# PDOC.net
KiCad netlist of a schematic drawn in Altium Designer
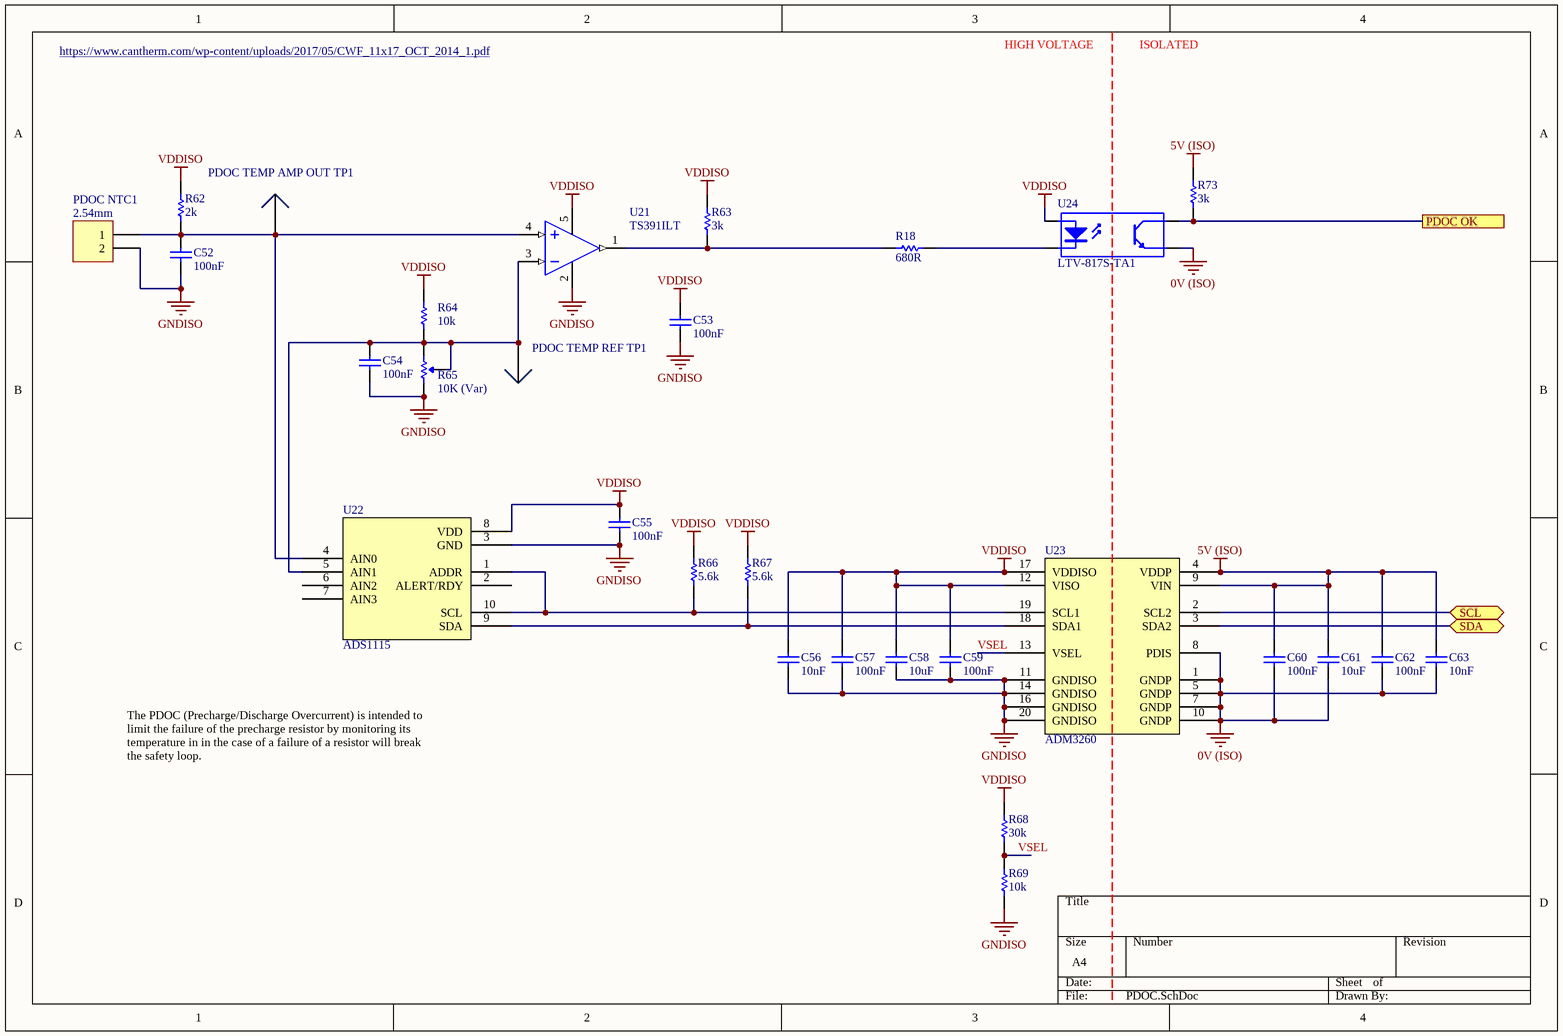
[diagram p0: PDOC.SchDoc]

(export (version "E")
  (design (tool "Eeschema 10.0.6"))
  (components
    (comp (ref "C52")
      (value "100nF")
      (footprint "0805")
      (fields
        (field (name "PART NUMBER") "GCM21BR71E104KA37L")
        (field (name "TOLERANCE") "10%")
        (field (name "MANUFACTURER") "muRata")
      )
      (libsource (lib "ts_20-standard-library") (part "Capacitor"))
    )
    (comp (ref "C53")
      (value "100nF")
      (footprint "0805")
      (fields
        (field (name "PART NUMBER") "GCM21BR71E104KA37L")
        (field (name "TOLERANCE") "10%")
        (field (name "MANUFACTURER") "muRata")
      )
      (libsource (lib "ts_20-standard-library") (part "Capacitor"))
    )
    (comp (ref "C54")
      (value "100nF")
      (footprint "0805")
      (fields
        (field (name "PART NUMBER") "GCM21BR71E104KA37L")
        (field (name "TOLERANCE") "10%")
        (field (name "MANUFACTURER") "muRata")
      )
      (libsource (lib "ts_20-standard-library") (part "Capacitor"))
    )
    (comp (ref "C55")
      (value "100nF")
      (footprint "0805")
      (fields
        (field (name "PART NUMBER") "GCM21BR71E104KA37L")
        (field (name "TOLERANCE") "10%")
        (field (name "MANUFACTURER") "muRata")
      )
      (libsource (lib "ts_20-standard-library") (part "Capacitor"))
    )
    (comp (ref "C56")
      (value "10nF")
      (footprint "0805")
      (fields
        (field (name "PART NUMBER") "GCM21BR71H103KA37L")
        (field (name "TOLERANCE") "10%")
        (field (name "MANUFACTURER") "muRata")
      )
      (libsource (lib "ts_20-standard-library") (part "Capacitor"))
    )
    (comp (ref "C57")
      (value "100nF")
      (footprint "0805")
      (fields
        (field (name "PART NUMBER") "GCM21BR71E104KA37L")
        (field (name "TOLERANCE") "10%")
        (field (name "MANUFACTURER") "muRata")
      )
      (libsource (lib "ts_20-standard-library") (part "Capacitor"))
    )
    (comp (ref "C58")
      (value "10uF")
      (footprint "0805")
      (fields
        (field (name "PART NUMBER") "GRM21BR6YA106KE43L")
        (field (name "TOLERANCE") "10%")
        (field (name "MANUFACTURER") "muRata")
      )
      (libsource (lib "ts_20-standard-library") (part "Capacitor"))
    )
    (comp (ref "C59")
      (value "100nF")
      (footprint "0805")
      (fields
        (field (name "PART NUMBER") "GCM21BR71E104KA37L")
        (field (name "TOLERANCE") "10%")
        (field (name "MANUFACTURER") "muRata")
      )
      (libsource (lib "ts_20-standard-library") (part "Capacitor"))
    )
    (comp (ref "C60")
      (value "100nF")
      (footprint "0805")
      (fields
        (field (name "PART NUMBER") "GCM21BR71E104KA37L")
        (field (name "TOLERANCE") "10%")
        (field (name "MANUFACTURER") "muRata")
      )
      (libsource (lib "ts_20-standard-library") (part "Capacitor"))
    )
    (comp (ref "C61")
      (value "10uF")
      (footprint "0805")
      (fields
        (field (name "PART NUMBER") "GRM21BR6YA106KE43L")
        (field (name "TOLERANCE") "10%")
        (field (name "MANUFACTURER") "muRata")
      )
      (libsource (lib "ts_20-standard-library") (part "Capacitor"))
    )
    (comp (ref "C62")
      (value "100nF")
      (footprint "0805")
      (fields
        (field (name "PART NUMBER") "GCM21BR71E104KA37L")
        (field (name "TOLERANCE") "10%")
        (field (name "MANUFACTURER") "muRata")
      )
      (libsource (lib "ts_20-standard-library") (part "Capacitor"))
    )
    (comp (ref "C63")
      (value "10nF")
      (footprint "0805")
      (fields
        (field (name "PART NUMBER") "GCM21BR71H103KA37L")
        (field (name "TOLERANCE") "10%")
        (field (name "MANUFACTURER") "muRata")
      )
      (libsource (lib "ts_20-standard-library") (part "Capacitor"))
    )
    (comp (ref "PDOC NTC1")
      (value "2.54mm")
      (footprint "TH 2.54mm Header 1x2")
      (fields (field (name "PART NUMBER") "TH 2.54mm Header 1x2") (field (name "CONTACT") "NA"))
      (libsource (lib "ts_20-standard-connectors") (part "Header 1x2"))
    )
    (comp (ref "PDOC TEMP AMP OUT TP1")
      (value "0mm")
      (footprint "SMD Test Point")
      (fields (field (name "PART NUMBER") "SMD Test Point") (field (name "CONTACT") "NA"))
      (libsource (lib "ts_20-standard-connectors") (part "Test Point"))
    )
    (comp (ref "PDOC TEMP REF TP1")
      (value "0mm")
      (footprint "SMD Test Point")
      (fields (field (name "PART NUMBER") "SMD Test Point") (field (name "CONTACT") "NA"))
      (libsource (lib "ts_20-standard-connectors") (part "Test Point"))
    )
    (comp (ref "R18")
      (value "680R")
      (footprint "0805")
      (fields
        (field (name "PART NUMBER") "RC0805FR07680RL")
        (field (name "MANUFACTURER") "YAGEO")
        (field (name "TOLERANCE") "0.01")
      )
      (libsource (lib "ts_20-standard-library") (part "Resistor"))
    )
    (comp (ref "R62")
      (value "2k")
      (footprint "0805")
      (fields
        (field (name "PART NUMBER") "RC0805FR072KL")
        (field (name "MANUFACTURER") "YAGEO")
        (field (name "TOLERANCE") "0.01")
      )
      (libsource (lib "ts_20-standard-library") (part "Resistor"))
    )
    (comp (ref "R63")
      (value "3k")
      (footprint "0805")
      (fields
        (field (name "PART NUMBER") "RC0805FR073KL")
        (field (name "MANUFACTURER") "YAGEO")
        (field (name "TOLERANCE") "0.01")
      )
      (libsource (lib "ts_20-standard-library") (part "Resistor"))
    )
    (comp (ref "R64")
      (value "10k")
      (footprint "0805")
      (fields
        (field (name "PART NUMBER") "RC0805FR0710KL")
        (field (name "MANUFACTURER") "YAGEO")
        (field (name "TOLERANCE") "0.01")
      )
      (libsource (lib "ts_20-standard-library") (part "Resistor"))
    )
    (comp (ref "R65")
      (value "10K (Var)")
      (footprint "B 3296")
      (fields
        (field (name "PART NUMBER") "3296W-1-103LF")
        (field (name "MANUFACTURER") "Bournes Inc")
        (field (name "TOLERANCE") "0.1")
      )
      (libsource (lib "ts_20-standard-library") (part "Resistor (Potentiometer)"))
    )
    (comp (ref "R66")
      (value "5.6k")
      (footprint "0805")
      (fields
        (field (name "PART NUMBER") "RC0805FR075K6L")
        (field (name "MANUFACTURER") "YAGEO")
        (field (name "TOLERANCE") "0.01")
      )
      (libsource (lib "ts_20-standard-library") (part "Resistor"))
    )
    (comp (ref "R67")
      (value "5.6k")
      (footprint "0805")
      (fields
        (field (name "PART NUMBER") "RC0805FR075K6L")
        (field (name "MANUFACTURER") "YAGEO")
        (field (name "TOLERANCE") "0.01")
      )
      (libsource (lib "ts_20-standard-library") (part "Resistor"))
    )
    (comp (ref "R68")
      (value "30k")
      (footprint "0805")
      (fields
        (field (name "PART NUMBER") "RC0805FR0730KL")
        (field (name "MANUFACTURER") "YAGEO")
        (field (name "TOLERANCE") "0.01")
      )
      (libsource (lib "ts_20-standard-library") (part "Resistor"))
    )
    (comp (ref "R69")
      (value "10k")
      (footprint "0805")
      (fields
        (field (name "PART NUMBER") "RC0805FR0710KL")
        (field (name "MANUFACTURER") "YAGEO")
        (field (name "TOLERANCE") "0.01")
      )
      (libsource (lib "ts_20-standard-library") (part "Resistor"))
    )
    (comp (ref "R73")
      (value "3k")
      (footprint "0805")
      (fields
        (field (name "PART NUMBER") "RC0805FR073KL")
        (field (name "MANUFACTURER") "YAGEO")
        (field (name "TOLERANCE") "0.01")
      )
      (libsource (lib "ts_20-standard-library") (part "Resistor"))
    )
    (comp (ref "U21")
      (value "TS391ILT")
      (footprint "ON SOT-23-5")
      (description "IC COMP LO PWR SGL V SOT 23-5L")
      (fields
        (field (name "MANUFACTURER") "STMicroelectronics")
        (field (name "DIGIKEY PART NUMBER") "497-2275-2-ND")
      )
      (libsource (lib "ts_20-standard-library") (part "TS391ILT"))
    )
    (comp (ref "U22")
      (value "ADS1115")
      (footprint "TI 10-VSSOP")
      (description "16 Bit Analog to Digital Converter 2, 4 Input 1 Sigma-Delta 10-VSSOP")
      (fields
        (field (name "MANUFACTURER") "Texas Instruments")
        (field (name "DIGIKEY PART NUMBER") "296-38849-1-ND")
      )
      (libsource (lib "ts_20-standard-library") (part "ADS1115"))
    )
    (comp (ref "U23")
      (value "ADM3260")
      (footprint "AD 20-SSOP")
      (description "I²C Digital Isolator 2500Vrms 2 Channel 25kV/µs CMTI 20-SSOP (0.209\", 5.30mm Width)")
      (fields
        (field (name "MANUFACTURER") "Analog Devices")
        (field (name "DIGIKEY PART NUMBER") "ADM3260ARSZ-RL7CT-ND")
      )
      (libsource (lib "ts_20-standard-library") (part "ADM3260"))
    )
    (comp (ref "U24")
      (value "LTV-817S-TA1")
      (footprint "ON 4-SMD")
      (description "35V 50ma Optocoupler (VF=1.2V)")
      (fields
        (field (name "MANUFACTURER") "Lite-On Inc")
        (field (name "DIGIKEY PART NUMBER") "160-1893-2-ND")
      )
      (libsource (lib "ts_20-standard-library") (part "LTV-817S-TA1"))
    )
  )
  (nets
    (net (code "1") (name "/PDOC OK") (class "Default")
      (node (ref "R73") (pin "1") (pinfunction "1_1") (pintype "passive"))
      (node (ref "U24") (pin "4") (pinfunction "C_4") (pintype "passive"))
    )
    (net (code "2") (name "/SCL") (class "Default")
      (node (ref "U23") (pin "2") (pinfunction "SCL2_2") (pintype "passive"))
    )
    (net (code "3") (name "/SDA") (class "Default")
      (node (ref "U23") (pin "3") (pinfunction "SDA2_3") (pintype "passive"))
    )
    (net (code "4") (name "/VSEL") (class "Default")
      (node (ref "R68") (pin "1") (pinfunction "1_1") (pintype "passive"))
      (node (ref "R69") (pin "2") (pinfunction "2_2") (pintype "passive"))
      (node (ref "U23") (pin "13") (pinfunction "VSEL_13") (pintype "passive"))
    )
    (net (code "5") (name "0V (ISO)") (class "Default")
      (node (ref "C60") (pin "1") (pinfunction "1_1") (pintype "passive"))
      (node (ref "C61") (pin "1") (pinfunction "1_1") (pintype "passive"))
      (node (ref "C62") (pin "1") (pinfunction "1_1") (pintype "passive"))
      (node (ref "C63") (pin "1") (pinfunction "1_1") (pintype "passive"))
      (node (ref "U23") (pin "1") (pinfunction "GNDP_1") (pintype "passive"))
      (node (ref "U23") (pin "10") (pinfunction "GNDP_10") (pintype "passive"))
      (node (ref "U23") (pin "5") (pinfunction "GNDP_5") (pintype "passive"))
      (node (ref "U23") (pin "7") (pinfunction "GNDP_7") (pintype "passive"))
      (node (ref "U23") (pin "8") (pinfunction "PDIS_8") (pintype "passive"))
      (node (ref "U24") (pin "3") (pinfunction "E_3") (pintype "passive"))
    )
    (net (code "6") (name "5V (ISO)") (class "Default")
      (node (ref "C60") (pin "2") (pinfunction "2_2") (pintype "passive"))
      (node (ref "C61") (pin "2") (pinfunction "2_2") (pintype "passive"))
      (node (ref "C62") (pin "2") (pinfunction "2_2") (pintype "passive"))
      (node (ref "C63") (pin "2") (pinfunction "2_2") (pintype "passive"))
      (node (ref "R73") (pin "2") (pinfunction "2_2") (pintype "passive"))
      (node (ref "U23") (pin "4") (pinfunction "VDDP_4") (pintype "passive"))
      (node (ref "U23") (pin "9") (pinfunction "VIN_9") (pintype "passive"))
    )
    (net (code "7") (name "GNDISO") (class "Default")
      (node (ref "C52") (pin "1") (pinfunction "1_1") (pintype "passive"))
      (node (ref "C53") (pin "1") (pinfunction "1_1") (pintype "passive"))
      (node (ref "C54") (pin "1") (pinfunction "1_1") (pintype "passive"))
      (node (ref "C55") (pin "2") (pinfunction "2_2") (pintype "passive"))
      (node (ref "C56") (pin "1") (pinfunction "1_1") (pintype "passive"))
      (node (ref "C57") (pin "1") (pinfunction "1_1") (pintype "passive"))
      (node (ref "C58") (pin "1") (pinfunction "1_1") (pintype "passive"))
      (node (ref "C59") (pin "2") (pinfunction "2_2") (pintype "passive"))
      (node (ref "PDOC NTC1") (pin "2") (pinfunction "2_2") (pintype "passive"))
      (node (ref "R65") (pin "3") (pinfunction "CW_3") (pintype "passive"))
      (node (ref "R69") (pin "1") (pinfunction "1_1") (pintype "passive"))
      (node (ref "U21") (pin "2") (pinfunction "VCC-_2") (pintype "power_in"))
      (node (ref "U22") (pin "3") (pinfunction "GND_3") (pintype "passive"))
      (node (ref "U23") (pin "11") (pinfunction "GNDISO_11") (pintype "passive"))
      (node (ref "U23") (pin "14") (pinfunction "GNDISO_14") (pintype "passive"))
      (node (ref "U23") (pin "16") (pinfunction "GNDISO_16") (pintype "passive"))
      (node (ref "U23") (pin "20") (pinfunction "GNDISO_20") (pintype "passive"))
    )
    (net (code "8") (name "Net-(R65-CCW)") (class "Default")
      (node (ref "C54") (pin "2") (pinfunction "2_2") (pintype "passive"))
      (node (ref "PDOC TEMP REF TP1") (pin "1") (pinfunction "1_1") (pintype "passive"))
      (node (ref "R64") (pin "1") (pinfunction "1_1") (pintype "passive"))
      (node (ref "R65") (pin "1") (pinfunction "CCW_1") (pintype "passive"))
      (node (ref "R65") (pin "2") (pinfunction "Wiper_2") (pintype "passive"))
      (node (ref "U21") (pin "3") (pinfunction "IN-_3") (pintype "input"))
      (node (ref "U22") (pin "5") (pinfunction "AIN1_5") (pintype "passive"))
    )
    (net (code "9") (name "Net-(U21-IIN+)") (class "Default")
      (node (ref "C52") (pin "2") (pinfunction "2_2") (pintype "passive"))
      (node (ref "PDOC NTC1") (pin "1") (pinfunction "1_1") (pintype "passive"))
      (node (ref "PDOC TEMP AMP OUT TP1") (pin "1") (pinfunction "1_1") (pintype "passive"))
      (node (ref "R62") (pin "1") (pinfunction "1_1") (pintype "passive"))
      (node (ref "U21") (pin "4") (pinfunction "IIN+_4") (pintype "input"))
      (node (ref "U22") (pin "4") (pinfunction "AIN0_4") (pintype "passive"))
    )
    (net (code "10") (name "Net-(U21-OUT)") (class "Default")
      (node (ref "R18") (pin "1") (pinfunction "1_1") (pintype "passive"))
      (node (ref "R63") (pin "1") (pinfunction "1_1") (pintype "passive"))
      (node (ref "U21") (pin "1") (pinfunction "OUT_1") (pintype "output"))
    )
    (net (code "11") (name "Net-(U22-ADDR)") (class "Default")
      (node (ref "R66") (pin "1") (pinfunction "1_1") (pintype "passive"))
      (node (ref "U22") (pin "1") (pinfunction "ADDR_1") (pintype "passive"))
      (node (ref "U22") (pin "10") (pinfunction "SCL_10") (pintype "passive"))
      (node (ref "U23") (pin "19") (pinfunction "SCL1_19") (pintype "passive"))
    )
    (net (code "12") (name "Net-(U22-SDA)") (class "Default")
      (node (ref "R67") (pin "1") (pinfunction "1_1") (pintype "passive"))
      (node (ref "U22") (pin "9") (pinfunction "SDA_9") (pintype "passive"))
      (node (ref "U23") (pin "18") (pinfunction "SDA1_18") (pintype "passive"))
    )
    (net (code "13") (name "Net-(U24-K)") (class "Default")
      (node (ref "R18") (pin "2") (pinfunction "2_2") (pintype "passive"))
      (node (ref "U24") (pin "2") (pinfunction "K_2") (pintype "passive"))
    )
    (net (code "14") (name "VDDISO") (class "Default")
      (node (ref "C53") (pin "2") (pinfunction "2_2") (pintype "passive"))
      (node (ref "C55") (pin "1") (pinfunction "1_1") (pintype "passive"))
      (node (ref "C56") (pin "2") (pinfunction "2_2") (pintype "passive"))
      (node (ref "C57") (pin "2") (pinfunction "2_2") (pintype "passive"))
      (node (ref "C58") (pin "2") (pinfunction "2_2") (pintype "passive"))
      (node (ref "C59") (pin "1") (pinfunction "1_1") (pintype "passive"))
      (node (ref "R62") (pin "2") (pinfunction "2_2") (pintype "passive"))
      (node (ref "R63") (pin "2") (pinfunction "2_2") (pintype "passive"))
      (node (ref "R64") (pin "2") (pinfunction "2_2") (pintype "passive"))
      (node (ref "R66") (pin "2") (pinfunction "2_2") (pintype "passive"))
      (node (ref "R67") (pin "2") (pinfunction "2_2") (pintype "passive"))
      (node (ref "R68") (pin "2") (pinfunction "2_2") (pintype "passive"))
      (node (ref "U21") (pin "5") (pinfunction "VCC+_5") (pintype "power_in"))
      (node (ref "U22") (pin "8") (pinfunction "VDD_8") (pintype "passive"))
      (node (ref "U23") (pin "12") (pinfunction "VISO_12") (pintype "passive"))
      (node (ref "U23") (pin "17") (pinfunction "VDDISO_17") (pintype "passive"))
      (node (ref "U24") (pin "1") (pinfunction "A_1") (pintype "passive"))
    )
    (net (code "15") (name "unconnected-(U22-AIN2-Pad6)") (class "Default")
      (node (ref "U22") (pin "6") (pinfunction "AIN2_6") (pintype "passive"))
    )
    (net (code "16") (name "unconnected-(U22-AIN3-Pad7)") (class "Default")
      (node (ref "U22") (pin "7") (pinfunction "AIN3_7") (pintype "passive"))
    )
    (net (code "17") (name "unconnected-(U22-ALERT{slash}RDY-Pad2)") (class "Default")
      (node (ref "U22") (pin "2") (pinfunction "ALERT/RDY_2") (pintype "passive"))
    )
  )
)
